# IR.net
KiCad netlist of a schematic drawn in EAGLE
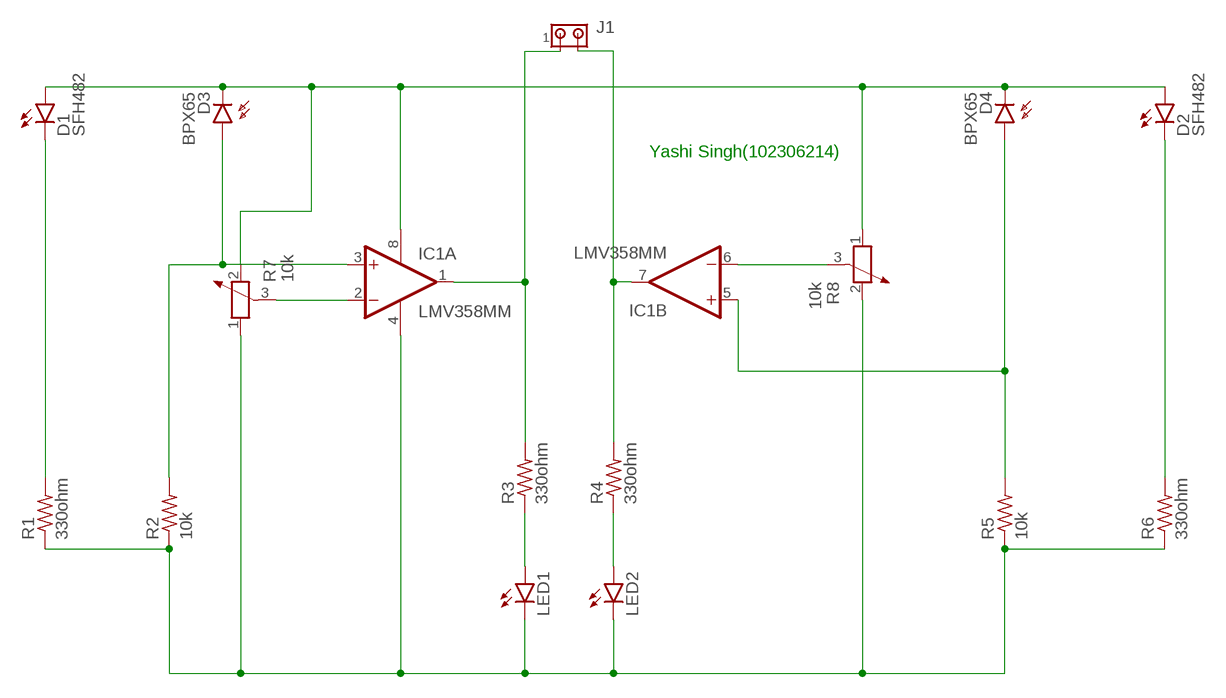
[diagram p0: schematic, sheet 1]

(export (version "E")
  (design (tool "Eeschema 10.0.6"))
  (components
    (comp (ref "D1")
      (value "SFH482")
      (footprint "eagle-import:SFH482")
      (libsource (lib "eagle-import") (part "SFH482"))
    )
    (comp (ref "D2")
      (value "SFH482")
      (footprint "eagle-import:SFH482")
      (libsource (lib "eagle-import") (part "SFH482"))
    )
    (comp (ref "D3")
      (value "BPX65")
      (footprint "eagle-import:BPX65")
      (fields (field (name "MPN") "BPX65."))
      (libsource (lib "eagle-import") (part "BPX65"))
    )
    (comp (ref "D4")
      (value "BPX65")
      (footprint "eagle-import:BPX65")
      (fields (field (name "MPN") "BPX65."))
      (libsource (lib "eagle-import") (part "BPX65"))
    )
    (comp (ref "IC1")
      (value "LMV358MM")
      (footprint "eagle-import:MSOP08")
      (libsource (lib "eagle-import") (part "LMV358?MM"))
    )
    (comp (ref "J1")
      (value "MTA02-100")
      (footprint "eagle-import:10X02MTA")
      (libsource (lib "eagle-import") (part "MTA02-100"))
    )
    (comp (ref "LED1")
      (value "LED3MM")
      (footprint "eagle-import:LED3MM")
      (libsource (lib "eagle-import") (part "LED3MM"))
    )
    (comp (ref "LED2")
      (value "LED3MM")
      (footprint "eagle-import:LED3MM")
      (libsource (lib "eagle-import") (part "LED3MM"))
    )
    (comp (ref "R1")
      (value "330ohm")
      (footprint "eagle-import:0207_10")
      (libsource (lib "eagle-import") (part "R-US_0207/10"))
    )
    (comp (ref "R2")
      (value "10k")
      (footprint "eagle-import:0207_10")
      (libsource (lib "eagle-import") (part "R-US_0207/10"))
    )
    (comp (ref "R3")
      (value "330ohm")
      (footprint "eagle-import:0207_10")
      (libsource (lib "eagle-import") (part "R-US_0207/10"))
    )
    (comp (ref "R4")
      (value "330ohm")
      (footprint "eagle-import:0207_10")
      (libsource (lib "eagle-import") (part "R-US_0207/10"))
    )
    (comp (ref "R5")
      (value "10k")
      (footprint "eagle-import:0207_10")
      (libsource (lib "eagle-import") (part "R-US_0207/10"))
    )
    (comp (ref "R6")
      (value "330ohm")
      (footprint "eagle-import:0207_10")
      (libsource (lib "eagle-import") (part "R-US_0207/10"))
    )
    (comp (ref "R7")
      (value "10k")
      (footprint "eagle-import:PT-10")
      (libsource (lib "eagle-import") (part "POTENTIOMETER_PT-10"))
    )
    (comp (ref "R8")
      (value "10k")
      (footprint "eagle-import:PT-10")
      (libsource (lib "eagle-import") (part "POTENTIOMETER_PT-10"))
    )
  )
  (nets
    (net (code "1") (name "Net-(D1-C)") (class "Default")
      (node (ref "D1") (pin "K") (pinfunction "C_K") (pintype "passive"))
      (node (ref "R1") (pin "2") (pinfunction "2_2") (pintype "passive"))
    )
    (net (code "2") (name "Net-(D2-C)") (class "Default")
      (node (ref "D2") (pin "K") (pinfunction "C_K") (pintype "passive"))
      (node (ref "R6") (pin "2") (pinfunction "2_2") (pintype "passive"))
    )
    (net (code "3") (name "Net-(D3-C)") (class "Default")
      (node (ref "D1") (pin "A") (pinfunction "A_A") (pintype "passive"))
      (node (ref "D2") (pin "A") (pinfunction "A_A") (pintype "passive"))
      (node (ref "D3") (pin "K") (pinfunction "C_K") (pintype "passive"))
      (node (ref "D4") (pin "K") (pinfunction "C_K") (pintype "passive"))
      (node (ref "IC1") (pin "8") (pinfunction "V+_8") (pintype "power_in"))
      (node (ref "R7") (pin "2") (pinfunction "2_2") (pintype "passive"))
      (node (ref "R8") (pin "1") (pinfunction "1_1") (pintype "passive"))
    )
    (net (code "4") (name "Net-(IC1A-+IN)") (class "Default")
      (node (ref "D3") (pin "A") (pinfunction "A_A") (pintype "passive"))
      (node (ref "IC1") (pin "3") (pinfunction "+IN_3") (pintype "input"))
      (node (ref "R2") (pin "2") (pinfunction "2_2") (pintype "passive"))
    )
    (net (code "5") (name "Net-(IC1A--IN)") (class "Default")
      (node (ref "IC1") (pin "2") (pinfunction "-IN_2") (pintype "input"))
      (node (ref "R7") (pin "3") (pinfunction "3_3") (pintype "passive"))
    )
    (net (code "6") (name "Net-(IC1A-OUT)") (class "Default")
      (node (ref "IC1") (pin "1") (pinfunction "OUT_1") (pintype "output"))
      (node (ref "J1") (pin "1") (pinfunction "1_1") (pintype "passive"))
      (node (ref "R3") (pin "2") (pinfunction "2_2") (pintype "passive"))
    )
    (net (code "7") (name "Net-(IC1B-+IN)") (class "Default")
      (node (ref "D4") (pin "A") (pinfunction "A_A") (pintype "passive"))
      (node (ref "IC1") (pin "5") (pinfunction "+IN_5") (pintype "input"))
      (node (ref "R5") (pin "2") (pinfunction "2_2") (pintype "passive"))
    )
    (net (code "8") (name "Net-(IC1B--IN)") (class "Default")
      (node (ref "IC1") (pin "6") (pinfunction "-IN_6") (pintype "input"))
      (node (ref "R8") (pin "3") (pinfunction "3_3") (pintype "passive"))
    )
    (net (code "9") (name "Net-(IC1B-OUT)") (class "Default")
      (node (ref "IC1") (pin "7") (pinfunction "OUT_7") (pintype "output"))
      (node (ref "J1") (pin "2") (pinfunction "2_2") (pintype "passive"))
      (node (ref "R4") (pin "2") (pinfunction "2_2") (pintype "passive"))
    )
    (net (code "10") (name "Net-(IC1C-V-)") (class "Default")
      (node (ref "IC1") (pin "4") (pinfunction "V-_4") (pintype "power_in"))
      (node (ref "LED1") (pin "K") (pinfunction "C_K") (pintype "passive"))
      (node (ref "LED2") (pin "K") (pinfunction "C_K") (pintype "passive"))
      (node (ref "R1") (pin "1") (pinfunction "1_1") (pintype "passive"))
      (node (ref "R2") (pin "1") (pinfunction "1_1") (pintype "passive"))
      (node (ref "R5") (pin "1") (pinfunction "1_1") (pintype "passive"))
      (node (ref "R6") (pin "1") (pinfunction "1_1") (pintype "passive"))
      (node (ref "R7") (pin "1") (pinfunction "1_1") (pintype "passive"))
      (node (ref "R8") (pin "2") (pinfunction "2_2") (pintype "passive"))
    )
    (net (code "11") (name "Net-(LED1-PadA)") (class "Default")
      (node (ref "LED1") (pin "A") (pinfunction "A_A") (pintype "passive"))
      (node (ref "R3") (pin "1") (pinfunction "1_1") (pintype "passive"))
    )
    (net (code "12") (name "Net-(LED2-PadA)") (class "Default")
      (node (ref "LED2") (pin "A") (pinfunction "A_A") (pintype "passive"))
      (node (ref "R4") (pin "1") (pinfunction "1_1") (pintype "passive"))
    )
  )
)
